# emitter_follower_v2_punto_di_lavoro.net
KiCad netlist of a schematic drawn in EAGLE
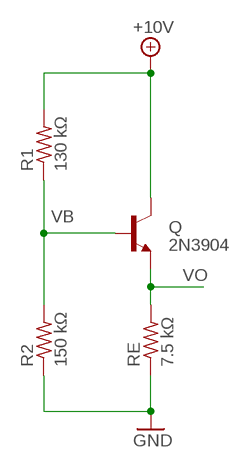
[diagram p0: schematic, sheet 1]

(export (version "E")
  (design (tool "Eeschema 10.0.6"))
  (components
    (comp (ref "Q")
      (value "2N3904")
      (footprint "eagle-import:TO92")
      (libsource (lib "eagle-import") (part "2N3904"))
    )
    (comp (ref "R1")
      (value "130 kΩ")
      (footprint "eagle-import:0204_5")
      (libsource (lib "eagle-import") (part "R-US_0204/5"))
    )
    (comp (ref "R2")
      (value "150 kΩ")
      (footprint "eagle-import:0204_5")
      (libsource (lib "eagle-import") (part "R-US_0204/5"))
    )
    (comp (ref "RE")
      (value "7.5 kΩ")
      (footprint "eagle-import:0204_5")
      (libsource (lib "eagle-import") (part "R-US_0204/5"))
    )
  )
  (nets
    (net (code "1") (name "+10V") (class "Default")
      (node (ref "Q") (pin "1") (pinfunction "C_1") (pintype "passive"))
      (node (ref "R1") (pin "2") (pinfunction "2_2") (pintype "passive"))
    )
    (net (code "2") (name "/VO") (class "Default")
      (node (ref "Q") (pin "3") (pinfunction "E_3") (pintype "passive"))
      (node (ref "RE") (pin "2") (pinfunction "2_2") (pintype "passive"))
    )
    (net (code "3") (name "GND") (class "Default")
      (node (ref "R2") (pin "1") (pinfunction "1_1") (pintype "passive"))
      (node (ref "RE") (pin "1") (pinfunction "1_1") (pintype "passive"))
    )
    (net (code "4") (name "Net-(Q-B)") (class "Default")
      (node (ref "Q") (pin "2") (pinfunction "B_2") (pintype "passive"))
      (node (ref "R1") (pin "1") (pinfunction "1_1") (pintype "passive"))
      (node (ref "R2") (pin "2") (pinfunction "2_2") (pintype "passive"))
    )
  )
)
